# gydrodrive_inputTrim.net
KiCad netlist of a schematic drawn in Altium Designer
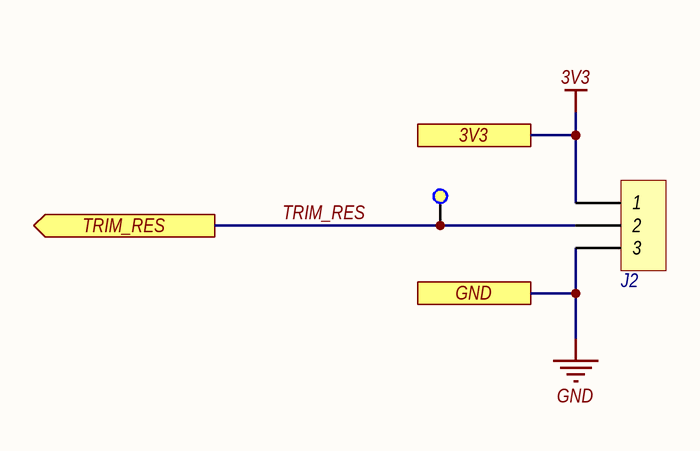
[diagram p0: gydrodrive_inputTrim.SchDoc]

(export (version "E")
  (design (tool "Eeschema 10.0.6"))
  (components
    (comp (ref "J2")
      (value "DG142V-5.08-03P")
      (footprint "DG142V-5.08-03P")
      (description "Клеммник 3-контактный, шаг 5.08 мм")
      (libsource (lib "StdLib") (part "PIN1x3"))
    )
    (comp (ref "TP5")
      (value "Test point 1")
      (footprint "TP_1")
      (description "Тестовый контакт круглый 1 мм")
      (libsource (lib "StdLib") (part "Test point"))
    )
  )
  (nets
    (net (code "1") (name "/TRIM_RES") (class "Default")
      (node (ref "J2") (pin "2") (pinfunction "2_2") (pintype "passive"))
      (node (ref "TP5") (pin "1") (pinfunction "1_1") (pintype "passive"))
    )
    (net (code "2") (name "3V3") (class "Default")
      (node (ref "J2") (pin "1") (pinfunction "1_1") (pintype "passive"))
    )
    (net (code "3") (name "GND") (class "Default")
      (node (ref "J2") (pin "3") (pinfunction "3_3") (pintype "passive"))
    )
  )
)
